# 4T_-.net
KiCad netlist of a schematic drawn in EasyEDA Pro
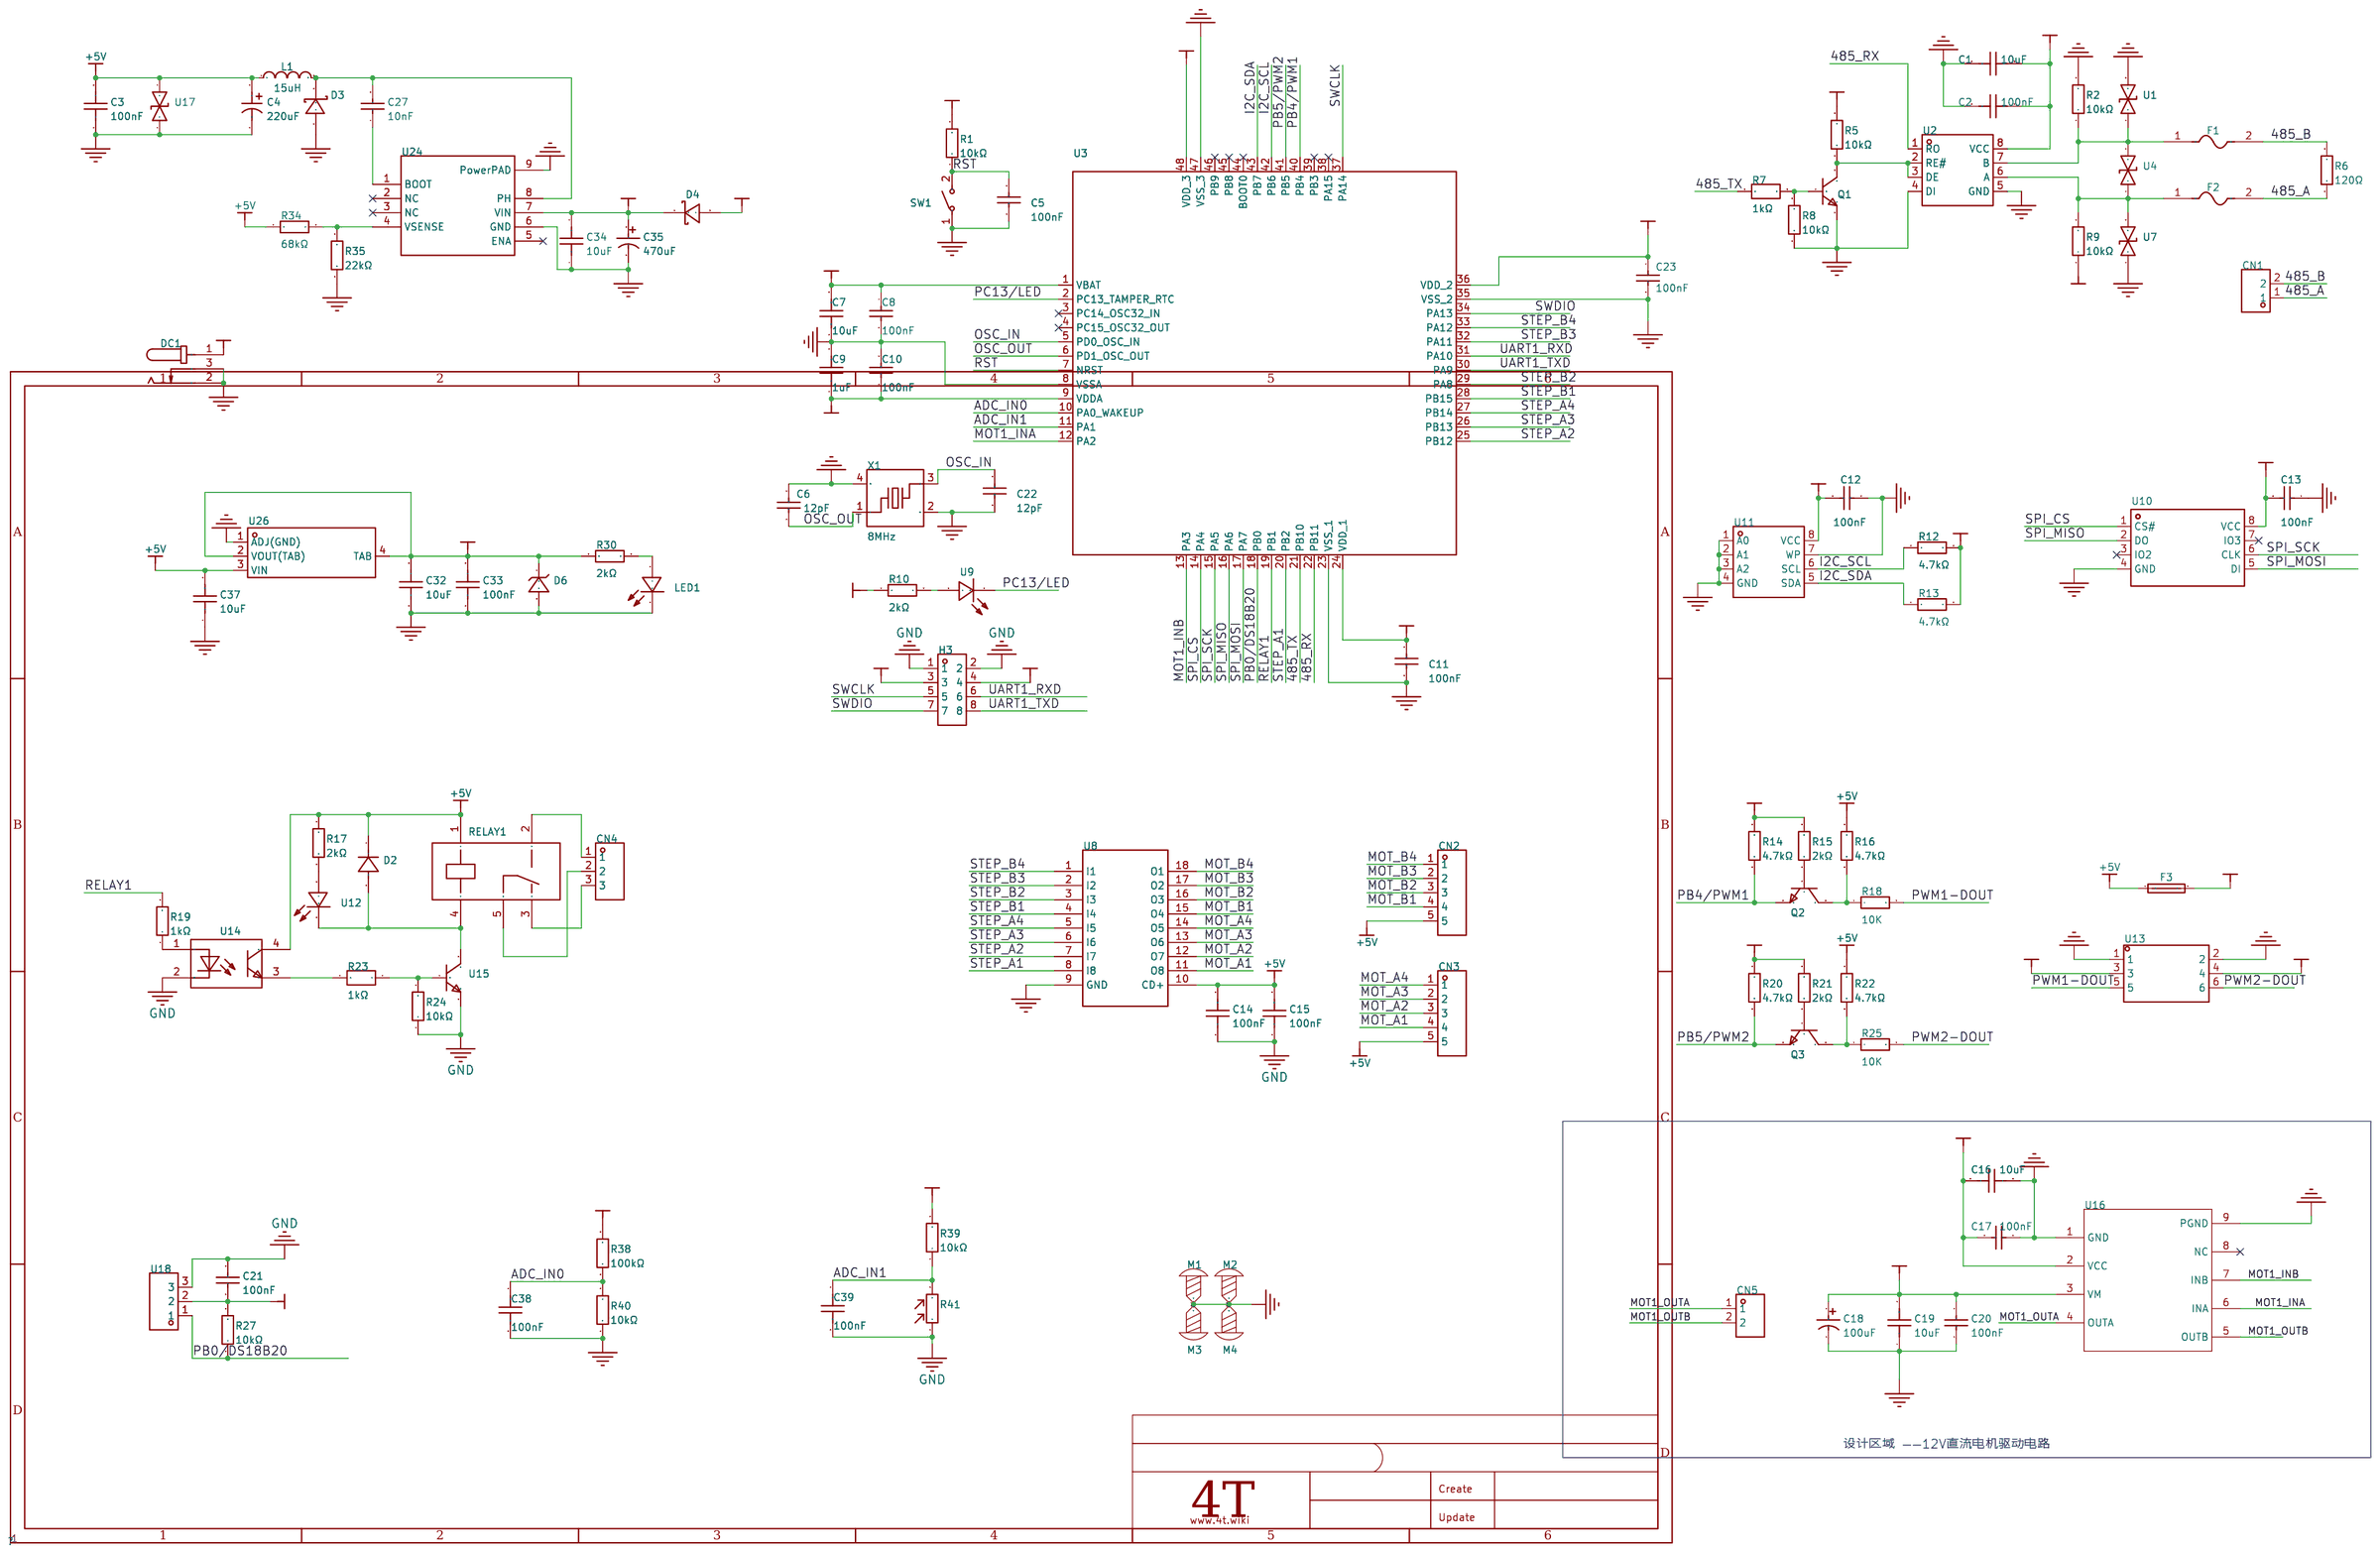
[diagram p0: schematic sheet]

(export (version "E")
  (design (tool "Eeschema 10.0.6"))
  (components
    (comp (ref "C1")
      (value "10uF")
      (footprint "easyedapro:C0603")
      (fields
        (field (name "Manufacturer Part") "CC0603KRX5R6BB106")
        (field (name "Manufacturer") "YAGEO(国巨)")
      )
      (libsource (lib "easyedapro") (part "CC0603KRX5R6BB106"))
    )
    (comp (ref "C2") (value "100nF") (libsource (lib "easyedapro") (part "CC0603KRX7R9BB104")))
    (comp (ref "C3")
      (value "100nF")
      (footprint "easyedapro:C0805")
      (fields
        (field (name "Manufacturer Part") "CC0805KRX7R9BB104")
        (field (name "Manufacturer") "YAGEO(国巨)")
      )
      (libsource (lib "easyedapro") (part "CC0805KRX7R9BB104"))
    )
    (comp (ref "C4")
      (value "220uF")
      (footprint "easyedapro:CAP-SMD_BD6.3-L6.6-W6.6-FD")
      (fields (field (name "Manufacturer Part") "189RV0019") (field (name "Manufacturer") "KNSCHA(科尼盛)"))
      (libsource (lib "easyedapro") (part "189RV0019"))
    )
    (comp (ref "C5") (value "100nF") (libsource (lib "easyedapro") (part "CC0603KRX7R8BB104")))
    (comp (ref "C6")
      (value "12pF")
      (footprint "easyedapro:C0603")
      (fields
        (field (name "Manufacturer Part") "CL10C120JB8NNNC")
        (field (name "Manufacturer") "SAMSUNG(三星)")
      )
      (libsource (lib "easyedapro") (part "CL10C120JB8NNNC"))
    )
    (comp (ref "C7")
      (value "10uF")
      (footprint "easyedapro:C0603")
      (fields
        (field (name "Manufacturer Part") "CL10A106KP8NNNC")
        (field (name "Manufacturer") "SAMSUNG(三星)")
      )
      (libsource (lib "easyedapro") (part "CL10A106KP8NNNC"))
    )
    (comp (ref "C8") (value "100nF") (libsource (lib "easyedapro") (part "CC0603KRX7R8BB104")))
    (comp (ref "C9")
      (value "1uF")
      (footprint "easyedapro:C0603")
      (fields
        (field (name "Manufacturer Part") "CC0603KRX7R9BB105")
        (field (name "Manufacturer") "YAGEO(国巨)")
      )
      (libsource (lib "easyedapro") (part "CC0603KRX7R9BB105"))
    )
    (comp (ref "C10") (value "100nF") (libsource (lib "easyedapro") (part "CC0603KRX7R8BB104")))
    (comp (ref "C11") (value "100nF") (libsource (lib "easyedapro") (part "CC0603KRX7R8BB104")))
    (comp (ref "C12") (value "100nF") (libsource (lib "easyedapro") (part "CC0603KRX7R8BB104")))
    (comp (ref "C13") (value "100nF") (libsource (lib "easyedapro") (part "CC0603KRX7R8BB104")))
    (comp (ref "C14")
      (value "100nF")
      (footprint "easyedapro:C0805")
      (fields
        (field (name "Manufacturer Part") "CL21A226MAQNNNE")
        (field (name "Manufacturer") "SAMSUNG(三星)")
      )
      (libsource (lib "easyedapro") (part "CL21A226MAQNNNE"))
    )
    (comp (ref "C15")
      (value "100nF")
      (footprint "easyedapro:C0805")
      (fields
        (field (name "Manufacturer Part") "CL21A226MAQNNNE")
        (field (name "Manufacturer") "SAMSUNG(三星)")
      )
      (libsource (lib "easyedapro") (part "CL21A226MAQNNNE"))
    )
    (comp (ref "C16")
      (value "10uF")
      (footprint "easyedapro:C0603")
      (fields
        (field (name "Manufacturer Part") "CL10A106MA8NRNC")
        (field (name "Manufacturer") "SAMSUNG(三星)")
      )
      (libsource (lib "easyedapro") (part "CL10A106MA8NRNC"))
    )
    (comp (ref "C17")
      (value "100nF")
      (footprint "easyedapro:C0603")
      (fields
        (field (name "Manufacturer Part") "CC0603KRX7R8BB104")
        (field (name "Manufacturer") "YAGEO(国巨)")
      )
      (libsource (lib "easyedapro") (part "CC0603KRX7R8BB104"))
    )
    (comp (ref "C18")
      (value "100uF")
      (footprint "easyedapro:CAP-SMD_BD6.3-L6.6-W6.6-LS7.2-R-RD")
      (fields (field (name "Manufacturer Part") "RVE1V101M0607") (field (name "Manufacturer") "ROQANG(容强)"))
      (libsource (lib "easyedapro") (part "RVE1V101M0607-C99837"))
    )
    (comp (ref "C19")
      (value "10uF")
      (footprint "easyedapro:C0603")
      (fields
        (field (name "Manufacturer Part") "CL10A106MA8NRNC")
        (field (name "Manufacturer") "SAMSUNG(三星)")
      )
      (libsource (lib "easyedapro") (part "CL10A106MA8NRNC"))
    )
    (comp (ref "C20")
      (value "100nF")
      (footprint "easyedapro:C0603")
      (fields
        (field (name "Manufacturer Part") "CC0603KRX7R8BB104")
        (field (name "Manufacturer") "YAGEO(国巨)")
      )
      (libsource (lib "easyedapro") (part "CC0603KRX7R8BB104"))
    )
    (comp (ref "C21") (value "100nF") (libsource (lib "easyedapro") (part "CC0603KRX7R8BB104")))
    (comp (ref "C22")
      (value "12pF")
      (footprint "easyedapro:C0603")
      (fields
        (field (name "Manufacturer Part") "CL10C120JB8NNNC")
        (field (name "Manufacturer") "SAMSUNG(三星)")
      )
      (libsource (lib "easyedapro") (part "CL10C120JB8NNNC"))
    )
    (comp (ref "C23") (value "100nF") (libsource (lib "easyedapro") (part "CC0603KRX7R8BB104")))
    (comp (ref "C27")
      (value "10nF")
      (footprint "easyedapro:C0603")
      (fields (field (name "Manufacturer Part") "0603B103K500NT") (field (name "Manufacturer") "FH(风华)"))
      (libsource (lib "easyedapro") (part "0603B103K500NT"))
    )
    (comp (ref "C32")
      (value "10uF")
      (footprint "easyedapro:C0603")
      (fields
        (field (name "Manufacturer Part") "CC0603MRX5R8BB106")
        (field (name "Manufacturer") "YAGEO(国巨)")
      )
      (libsource (lib "easyedapro") (part "CC0603MRX5R8BB106"))
    )
    (comp (ref "C33") (value "100nF") (libsource (lib "") (part "CC0603KRX7R9BB104_1")))
    (comp (ref "C34")
      (value "10uF")
      (footprint "easyedapro:C0805")
      (fields
        (field (name "Manufacturer Part") "GRM21BR61H106KE43L")
        (field (name "Manufacturer") "muRata(村田)")
      )
      (libsource (lib "easyedapro") (part "GRM21BR61H106KE43L"))
    )
    (comp (ref "C35")
      (value "470uF")
      (footprint "easyedapro:CAP-SMD_BD10.0-L10.3-W10.3-LS11.0-R-RD")
      (fields (field (name "Manufacturer Part") "RVT1V471M1010") (field (name "Manufacturer") "ROQANG(容强)"))
      (libsource (lib "easyedapro") (part "RVT1V471M1010-C72519"))
    )
    (comp (ref "C37")
      (value "10uF")
      (footprint "easyedapro:C0603")
      (fields
        (field (name "Manufacturer Part") "CC0603MRX5R8BB106")
        (field (name "Manufacturer") "YAGEO(国巨)")
      )
      (libsource (lib "easyedapro") (part "CC0603MRX5R8BB106"))
    )
    (comp (ref "C38")
      (value "100nF")
      (footprint "easyedapro:C0603")
      (fields
        (field (name "Manufacturer Part") "CC0603KRX7R9BB104")
        (field (name "Manufacturer") "YAGEO(国巨)")
      )
      (libsource (lib "easyedapro") (part "CC0603KRX7R9BB104"))
    )
    (comp (ref "C39")
      (value "100nF")
      (footprint "easyedapro:C0603")
      (fields
        (field (name "Manufacturer Part") "CC0603KRX7R9BB104")
        (field (name "Manufacturer") "YAGEO(国巨)")
      )
      (libsource (lib "easyedapro") (part "CC0603KRX7R9BB104"))
    )
    (comp (ref "CN1")
      (value "~")
      (footprint "easyedapro:CONN-TH_P5.00_KF2EDGR-5.0-2P")
      (fields (field (name "Manufacturer Part") "KF2EDGR-5.0-2P") (field (name "Manufacturer") "KEFA(科发)"))
      (libsource (lib "easyedapro") (part "KF2EDGR-5.0-2P"))
    )
    (comp (ref "CN2")
      (value "~")
      (footprint "easyedapro:CONN-TH_5P-P2.54_XH-5AW_C2908614")
      (fields (field (name "Manufacturer Part") "XH-5AW") (field (name "Manufacturer") "HCTL(华灿天禄)"))
      (libsource (lib "easyedapro") (part "XH-5AW_C2908614"))
    )
    (comp (ref "CN3")
      (value "~")
      (footprint "easyedapro:CONN-TH_5P-P2.54_XH-5AW_C2908614")
      (fields (field (name "Manufacturer Part") "XH-5AW") (field (name "Manufacturer") "HCTL(华灿天禄)"))
      (libsource (lib "easyedapro") (part "XH-5AW_C2908614"))
    )
    (comp (ref "CN4")
      (value "~")
      (footprint "easyedapro:CONN-TH_3P-P5.00_KF2EDGR-5.0-3P")
      (fields (field (name "Manufacturer Part") "KF2EDGR-5.0-3P") (field (name "Manufacturer") "KEFA(科发)"))
      (libsource (lib "easyedapro") (part "KF2EDGR-5.0-3P"))
    )
    (comp (ref "CN5")
      (value "~")
      (footprint "easyedapro:CONN-TH_2P-P2.50_ZX-XH2.54-2PWZ")
      (fields
        (field (name "Manufacturer Part") "ZX-XH2.54-2PWZ")
        (field (name "Manufacturer") "Megastar(兆星)")
      )
      (libsource (lib "easyedapro") (part "ZX-XH2.54-2PWZ"))
    )
    (comp (ref "D2") (value "1N4007") (libsource (lib "easyedapro") (part "1N4007_C727081")))
    (comp (ref "D3")
      (value "SS34")
      (footprint "easyedapro:SMA_L4.3-W2.6-LS5.2-RD")
      (fields (field (name "Manufacturer") "MDD(辰达半导体)"))
      (libsource (lib "easyedapro") (part "SS34_C8678"))
    )
    (comp (ref "D4")
      (value "SS34")
      (footprint "easyedapro:SMA_L4.3-W2.6-LS5.2-RD")
      (fields (field (name "Manufacturer") "MDD(辰达半导体)"))
      (libsource (lib "easyedapro") (part "SS34_C8678"))
    )
    (comp (ref "D6")
      (value "~")
      (footprint "easyedapro:SMB_L4.3-W3.6-LS5.3-RD")
      (fields (field (name "Manufacturer Part") "SMBJ3.3A") (field (name "Manufacturer") "RUILON(瑞隆源)"))
      (libsource (lib "easyedapro") (part "SMBJ3.3A_C2990571"))
    )
    (comp (ref "DC1")
      (value "~")
      (footprint "easyedapro:CONN-TH_DC-005-2.5A-2.0")
      (fields
        (field (name "Manufacturer Part") "DC-005-2.5A-2.0")
        (field (name "Manufacturer") "XKB Connectivity(中国星坤)")
      )
      (libsource (lib "easyedapro") (part "DC-005-2.5A-2.0"))
    )
    (comp (ref "F1")
      (value "~")
      (footprint "easyedapro:F0805")
      (fields (field (name "Manufacturer Part") "0805L100/12AR") (field (name "Manufacturer") "LUTE(陆特)"))
      (libsource (lib "easyedapro") (part "0805l100/12ar"))
    )
    (comp (ref "F2")
      (value "~")
      (footprint "easyedapro:F0805")
      (fields (field (name "Manufacturer Part") "0805L100/12AR") (field (name "Manufacturer") "LUTE(陆特)"))
      (libsource (lib "easyedapro") (part "0805l100/12ar"))
    )
    (comp (ref "F3")
      (value "~")
      (footprint "easyedapro:F0603")
      (fields (field (name "Manufacturer Part") "BSMD0603L-100") (field (name "Manufacturer") "BHFUSE(佰宏)"))
      (libsource (lib "easyedapro") (part "BSMD0603L-100"))
    )
    (comp (ref "H3")
      (value "~")
      (footprint "easyedapro:HDR-TH_8P-P2.54-V-M-R2-C4-S2.54")
      (fields (field (name "Manufacturer Part") "PZ254V-12-8P") (field (name "Manufacturer") "XFCN(兴飞)"))
      (libsource (lib "easyedapro") (part "PZ254V-12-8P"))
    )
    (comp (ref "L1")
      (value "15uH")
      (footprint "easyedapro:IND-SMD_L7.1-W6.6_SLO0618H")
      (fields
        (field (name "Manufacturer Part") "SLO0630H150MTT")
        (field (name "Manufacturer") "Sunltech(韩国顺磁)")
      )
      (libsource (lib "easyedapro") (part "SLO0630H150MTT"))
    )
    (comp (ref "LED1")
      (value "~")
      (footprint "easyedapro:LED0603-RD")
      (fields (field (name "Manufacturer Part") "KT-0603R") (field (name "Manufacturer") "KENTO"))
      (libsource (lib "easyedapro") (part "KT-0603R"))
    )
    (comp (ref "M1")
      (value "~")
      (footprint "easyedapro:LQ_M3螺丝")
      (description "Round,210")
      (libsource (lib "easyedapro") (part "M3螺丝孔"))
    )
    (comp (ref "M2")
      (value "~")
      (footprint "easyedapro:LQ_M3螺丝")
      (description "Round,210")
      (libsource (lib "easyedapro") (part "M3螺丝孔"))
    )
    (comp (ref "M3")
      (value "~")
      (footprint "easyedapro:LQ_M3螺丝")
      (description "Round,210")
      (libsource (lib "easyedapro") (part "M3螺丝孔"))
    )
    (comp (ref "M4")
      (value "~")
      (footprint "easyedapro:LQ_M3螺丝")
      (description "Round,210")
      (libsource (lib "easyedapro") (part "M3螺丝孔"))
    )
    (comp (ref "Q1")
      (value "~")
      (footprint "easyedapro:SOT-23-3_L2.9-W1.3-P1.90-LS2.4-BR")
      (fields (field (name "Manufacturer Part") "MMBT3904") (field (name "Manufacturer") "宏迦橙"))
      (libsource (lib "easyedapro") (part "MMBT3904_C7420353"))
    )
    (comp (ref "Q2")
      (value "S8050-J3Y")
      (footprint "easyedapro:SOT-23-3_L2.9-W1.6-P1.90-LS2.8-BR")
      (fields (field (name "Manufacturer Part") "S8050") (field (name "Manufacturer") "CJ(江苏长电/长晶)"))
      (libsource (lib "easyedapro") (part "S8050_C105433"))
    )
    (comp (ref "Q3")
      (value "S8050-J3Y")
      (footprint "easyedapro:SOT-23-3_L2.9-W1.6-P1.90-LS2.8-BR")
      (fields (field (name "Manufacturer Part") "S8050") (field (name "Manufacturer") "CJ(江苏长电/长晶)"))
      (libsource (lib "easyedapro") (part "S8050_C105433"))
    )
    (comp (ref "R1")
      (value "10kΩ")
      (footprint "easyedapro:R0603")
      (fields
        (field (name "Manufacturer Part") "0603WAF1002T5E")
        (field (name "Manufacturer") "UNI-ROYAL(厚声)")
      )
      (libsource (lib "easyedapro") (part "0603WAF1002T5E"))
    )
    (comp (ref "R2") (value "10kΩ") (libsource (lib "easyedapro") (part "RC0603JR-0710KL")))
    (comp (ref "R5")
      (value "10kΩ")
      (footprint "easyedapro:R0603")
      (fields (field (name "Manufacturer Part") "RC0603JR-0710KL") (field (name "Manufacturer") "YAGEO(国巨)"))
      (libsource (lib "easyedapro") (part "RC0603JR-0710KL"))
    )
    (comp (ref "R6")
      (value "120Ω")
      (footprint "easyedapro:R0805")
      (fields
        (field (name "Manufacturer Part") "0805W8F1200T5E")
        (field (name "Manufacturer") "UNI-ROYAL(厚声)")
      )
      (libsource (lib "easyedapro") (part "0805W8F1200T5E"))
    )
    (comp (ref "R7")
      (value "1kΩ")
      (footprint "easyedapro:R0603")
      (fields (field (name "Manufacturer Part") "RT0603BRE071KL") (field (name "Manufacturer") "YAGEO(国巨)"))
      (libsource (lib "easyedapro") (part "RT0603BRE071KL"))
    )
    (comp (ref "R8")
      (value "10kΩ")
      (footprint "easyedapro:R0603")
      (fields (field (name "Manufacturer Part") "RC0603JR-0710KL") (field (name "Manufacturer") "YAGEO(国巨)"))
      (libsource (lib "easyedapro") (part "RC0603JR-0710KL"))
    )
    (comp (ref "R9") (value "10kΩ") (libsource (lib "easyedapro") (part "RC0603JR-0710KL")))
    (comp (ref "R10")
      (value "2kΩ")
      (footprint "easyedapro:R0603")
      (fields
        (field (name "Manufacturer Part") "0603WAF2001T5E")
        (field (name "Manufacturer") "UNI-ROYAL(厚声)")
      )
      (libsource (lib "easyedapro") (part "0603WAF2001T5E"))
    )
    (comp (ref "R12")
      (value "4.7kΩ")
      (footprint "easyedapro:R0603")
      (fields (field (name "Manufacturer Part") "RC0603FR-074K7L") (field (name "Manufacturer") "YAGEO(国巨)"))
      (libsource (lib "easyedapro") (part "RC0603FR-074K7L"))
    )
    (comp (ref "R13")
      (value "4.7kΩ")
      (footprint "easyedapro:R0603")
      (fields (field (name "Manufacturer Part") "RC0603FR-074K7L") (field (name "Manufacturer") "YAGEO(国巨)"))
      (libsource (lib "easyedapro") (part "RC0603FR-074K7L"))
    )
    (comp (ref "R14")
      (value "4.7kΩ")
      (footprint "easyedapro:R0603")
      (fields (field (name "Manufacturer Part") "RC0603FR-074K7L") (field (name "Manufacturer") "YAGEO(国巨)"))
      (libsource (lib "easyedapro") (part "RC0603FR-074K7L"))
    )
    (comp (ref "R15")
      (value "2kΩ")
      (footprint "easyedapro:R0603")
      (fields (field (name "Manufacturer Part") "RC0603FR-072KL") (field (name "Manufacturer") "YAGEO(国巨)"))
      (libsource (lib "easyedapro") (part "RC0603FR-072KL"))
    )
    (comp (ref "R16")
      (value "4.7kΩ")
      (footprint "easyedapro:R0603")
      (fields (field (name "Manufacturer Part") "RC0603FR-074K7L") (field (name "Manufacturer") "YAGEO(国巨)"))
      (libsource (lib "easyedapro") (part "RC0603FR-074K7L"))
    )
    (comp (ref "R17")
      (value "2kΩ")
      (footprint "easyedapro:R0603")
      (fields
        (field (name "Manufacturer Part") "0603WAF2001T5E")
        (field (name "Manufacturer") "UNI-ROYAL(厚声)")
      )
      (libsource (lib "easyedapro") (part "0603WAF2001T5E"))
    )
    (comp (ref "R18")
      (value "10K")
      (footprint "easyedapro:R0603")
      (fields (field (name "Manufacturer Part") "RC0603FR-071KL") (field (name "Manufacturer") "YAGEO(国巨)"))
      (libsource (lib "easyedapro") (part "RC0603FR-071KL"))
    )
    (comp (ref "R19") (value "1kΩ") (libsource (lib "easyedapro") (part "RC0603FR-071KL")))
    (comp (ref "R20")
      (value "4.7kΩ")
      (footprint "easyedapro:R0603")
      (fields (field (name "Manufacturer Part") "RC0603FR-074K7L") (field (name "Manufacturer") "YAGEO(国巨)"))
      (libsource (lib "easyedapro") (part "RC0603FR-074K7L"))
    )
    (comp (ref "R21")
      (value "2kΩ")
      (footprint "easyedapro:R0603")
      (fields (field (name "Manufacturer Part") "RC0603FR-072KL") (field (name "Manufacturer") "YAGEO(国巨)"))
      (libsource (lib "easyedapro") (part "RC0603FR-072KL"))
    )
    (comp (ref "R22")
      (value "4.7kΩ")
      (footprint "easyedapro:R0603")
      (fields (field (name "Manufacturer Part") "RC0603FR-074K7L") (field (name "Manufacturer") "YAGEO(国巨)"))
      (libsource (lib "easyedapro") (part "RC0603FR-074K7L"))
    )
    (comp (ref "R23")
      (value "1kΩ")
      (footprint "easyedapro:R0603")
      (fields (field (name "Manufacturer Part") "RT0603BRE071KL") (field (name "Manufacturer") "YAGEO(国巨)"))
      (libsource (lib "easyedapro") (part "RT0603BRE071KL"))
    )
    (comp (ref "R24")
      (value "10kΩ")
      (footprint "easyedapro:R0603")
      (fields
        (field (name "Manufacturer Part") "0603WAF1002T5E")
        (field (name "Manufacturer") "UNI-ROYAL(厚声)")
      )
      (libsource (lib "easyedapro") (part "0603WAF1002T5E"))
    )
    (comp (ref "R25")
      (value "10K")
      (footprint "easyedapro:R0603")
      (fields (field (name "Manufacturer Part") "RC0603FR-071KL") (field (name "Manufacturer") "YAGEO(国巨)"))
      (libsource (lib "easyedapro") (part "RC0603FR-071KL"))
    )
    (comp (ref "R27")
      (value "10kΩ")
      (footprint "easyedapro:R0603")
      (fields
        (field (name "Manufacturer Part") "0603WAF1002T5E")
        (field (name "Manufacturer") "UNI-ROYAL(厚声)")
      )
      (libsource (lib "easyedapro") (part "0603WAF1002T5E"))
    )
    (comp (ref "R30") (value "2kΩ") (libsource (lib "easyedapro") (part "0603WAF2001T5E")))
    (comp (ref "R34")
      (value "68kΩ")
      (footprint "easyedapro:R0603")
      (fields
        (field (name "Manufacturer Part") "0603WAF6802T5E")
        (field (name "Manufacturer") "UNI-ROYAL(厚声)")
      )
      (libsource (lib "easyedapro") (part "0603WAF6802T5E"))
    )
    (comp (ref "R35")
      (value "22kΩ")
      (footprint "easyedapro:R0603")
      (fields (field (name "Manufacturer Part") "RC0603FR-0722KL") (field (name "Manufacturer") "YAGEO(国巨)"))
      (libsource (lib "easyedapro") (part "RC0603FR-0722KL"))
    )
    (comp (ref "R38")
      (value "100kΩ")
      (footprint "easyedapro:R0603")
      (fields (field (name "Manufacturer Part") "RC0603FR-07100KL") (field (name "Manufacturer") "YAGEO(国巨)"))
      (libsource (lib "easyedapro") (part "RC0603FR-07100KL"))
    )
    (comp (ref "R39")
      (value "10kΩ")
      (footprint "easyedapro:R0603")
      (fields
        (field (name "Manufacturer Part") "0603WAF1002T5E")
        (field (name "Manufacturer") "UNI-ROYAL(厚声)")
      )
      (libsource (lib "easyedapro") (part "0603WAF1002T5E"))
    )
    (comp (ref "R40")
      (value "10kΩ")
      (footprint "easyedapro:R0603")
      (fields
        (field (name "Manufacturer Part") "0603WAF1002T5E")
        (field (name "Manufacturer") "UNI-ROYAL(厚声)")
      )
      (libsource (lib "easyedapro") (part "0603WAF1002T5E"))
    )
    (comp (ref "R41") (value "~") (libsource (lib "easyedapro") (part "GL5516")))
    (comp (ref "RELAY1")
      (value "~")
      (footprint "easyedapro:RELAY-TH_SRD-XXVDC-XL-C")
      (fields (field (name "Manufacturer Part") "SRD-12VDC-SL-C") (field (name "Manufacturer") "松乐"))
      (libsource (lib "easyedapro") (part "SRD-12VDC-SL-C"))
    )
    (comp (ref "SW1")
      (value "~")
      (footprint "easyedapro:SW-SMD_L6.0-W3.5-LS8.0")
      (fields
        (field (name "Manufacturer Part") "GT-TC060B-H025-L1")
        (field (name "Manufacturer") "G-Switch(品赞)")
      )
      (libsource (lib "easyedapro") (part "GT-TC060B-H025-L1"))
    )
    (comp (ref "U1")
      (value "~")
      (footprint "easyedapro:SOD-123FL_L2.8-W1.8-LS3.7-BI")
      (fields (field (name "Manufacturer Part") "SMF6.0CA") (field (name "Manufacturer") "Liown(里阳半导体)"))
      (libsource (lib "easyedapro") (part "SMF6.0CA_C2990473"))
    )
    (comp (ref "U2")
      (value "~")
      (footprint "easyedapro:SOP-8_L4.9-W3.9-P1.27-LS6.0-BL")
      (fields (field (name "Manufacturer Part") "SP3485EN-MS") (field (name "Manufacturer") "MSKSEMI(美森科)"))
      (libsource (lib "easyedapro") (part "SP3485EN-MS"))
    )
    (comp (ref "U3")
      (value "~")
      (footprint "easyedapro:TQFP-48_L7.0-W7.0-P0.50-LS9.0-BL")
      (fields
        (field (name "Manufacturer Part") "GD32F103C8T6")
        (field (name "Manufacturer") "GigaDevice(兆易创新)")
      )
      (libsource (lib "easyedapro") (part "GD32F103C8T6"))
    )
    (comp (ref "U4")
      (value "~")
      (footprint "easyedapro:SOD-123FL_L2.8-W1.8-LS3.7-BI")
      (fields (field (name "Manufacturer Part") "SMF6.0CA") (field (name "Manufacturer") "Liown(里阳半导体)"))
      (libsource (lib "easyedapro") (part "SMF6.0CA_C2990473"))
    )
    (comp (ref "U7")
      (value "~")
      (footprint "easyedapro:SOD-123FL_L2.8-W1.8-LS3.7-BI")
      (fields (field (name "Manufacturer Part") "SMF6.0CA") (field (name "Manufacturer") "Liown(里阳半导体)"))
      (libsource (lib "easyedapro") (part "SMF6.0CA_C2990473"))
    )
    (comp (ref "U8")
      (value "~")
      (footprint "easyedapro:DIP-18_L23.0-W6.5-P2.54-LS7.6-BL")
      (fields (field (name "Manufacturer Part") "ULN2803G-D18-T") (field (name "Manufacturer") "UTC(友顺)"))
      (libsource (lib "easyedapro") (part "ULN2803G-D18-T"))
    )
    (comp (ref "U9")
      (value "~")
      (footprint "easyedapro:LED-TH_BD3.9-P2.54-RD_GREEN")
      (fields (field (name "Manufacturer Part") "L-3N4GD") (field (name "Manufacturer") "PARALIGHT(光鼎)"))
      (libsource (lib "easyedapro") (part "L-3N4GD"))
    )
    (comp (ref "U10")
      (value "~")
      (footprint "easyedapro:SOIC-8_L5.3-W5.3-P1.27-LS8.0-BL")
      (fields (field (name "Manufacturer Part") "W25Q128JVSIQ") (field (name "Manufacturer") "WINBOND(华邦)"))
      (libsource (lib "easyedapro") (part "W25Q128JVSIQTR"))
    )
    (comp (ref "U11")
      (value "AT24C02")
      (footprint "easyedapro:SOP-8_L5.0-W4.0-P1.27-LS6.0-BL")
      (fields (field (name "Manufacturer") "IDCHIP(英锐芯)"))
      (libsource (lib "easyedapro") (part "AT24C02"))
    )
    (comp (ref "U12")
      (value "~")
      (footprint "easyedapro:LED-TH_BD3.9-P2.54-RD_GREEN")
      (fields (field (name "Manufacturer Part") "L-3N4GD") (field (name "Manufacturer") "PARALIGHT(光鼎)"))
      (libsource (lib "easyedapro") (part "L-3N4GD"))
    )
    (comp (ref "U13")
      (value "~")
      (footprint "easyedapro:HDR-TH_6P-P2.54-H-R2-C3-S2.54-W10.0_MTP125-203R1")
      (fields (field (name "Manufacturer Part") "MTP125-1203R1") (field (name "Manufacturer") "MINTRON(明硕)"))
      (libsource (lib "easyedapro") (part "MTP125-203R1"))
    )
    (comp (ref "U14")
      (value "GX817C-S")
      (footprint "easyedapro:SOP-4_L6.5-W4.6-P2.54-LS10.2-TR")
      (fields (field (name "Manufacturer") "国芯佳品"))
      (libsource (lib "easyedapro") (part "GX817C-S"))
    )
    (comp (ref "U15")
      (value "~")
      (footprint "easyedapro:SOT-23-3_L2.9-W1.3-P1.90-LS2.4-BR")
      (fields (field (name "Manufacturer Part") "SS8050") (field (name "Manufacturer") "宏迦橙"))
      (libsource (lib "easyedapro") (part "SS8050_C7420370"))
    )
    (comp (ref "U16") (value "~") (libsource (lib "easyedapro") (part "BDR")))
    (comp (ref "U17")
      (value "~")
      (footprint "easyedapro:SOD-123FL_L2.8-W1.8-LS3.7-BI")
      (fields (field (name "Manufacturer Part") "SMF6.0CA") (field (name "Manufacturer") "Liown(里阳半导体)"))
      (libsource (lib "easyedapro") (part "SMF6.0CA_C2990473"))
    )
    (comp (ref "U18")
      (value "~")
      (footprint "easyedapro:CONN-TH_3P-P2.50_BX-XH2.54-3PWZ")
      (fields (field (name "Manufacturer Part") "BX-XH2.54-3PWZ") (field (name "Manufacturer") "Bossie(博锡)"))
      (libsource (lib "easyedapro") (part "BX-XH2.54-3P WZ"))
    )
    (comp (ref "U24")
      (value "~")
      (footprint "easyedapro:ESOP-8_L4.9-W3.9-P1.27-LS6.0-TL-EP")
      (fields (field (name "Manufacturer Part") "TPS5430DDAR") (field (name "Manufacturer") "TI(德州仪器)"))
      (libsource (lib "easyedapro") (part "TPS5430DDAR"))
    )
    (comp (ref "U26")
      (value "~")
      (footprint "easyedapro:SOT-223-4_L6.5-W3.5-P2.30-LS7.0-BR")
      (fields (field (name "Manufacturer Part") "AMS1117-3.3") (field (name "Manufacturer") "UMW(友台半导体)"))
      (libsource (lib "easyedapro") (part "AMS1117-3.3_C347222"))
    )
    (comp (ref "X1")
      (value "8MHz")
      (footprint "easyedapro:CRYSTAL-SMD_4P-L3.2-W2.5-BL")
      (fields (field (name "Manufacturer Part") "X32258MOB4SI") (field (name "Manufacturer") "YXC(扬兴晶振)"))
      (libsource (lib "easyedapro") (part "X32258MOB4SI"))
    )
  )
  (nets
    (net (code "1") (name "+5V") (class "Default")
      (node (ref "C14") (pin "2") (pinfunction "2_2") (pintype "unspecified"))
      (node (ref "C15") (pin "2") (pinfunction "2_2") (pintype "unspecified"))
      (node (ref "C3") (pin "2") (pinfunction "2_2") (pintype "unspecified"))
      (node (ref "C37") (pin "2") (pinfunction "2_2") (pintype "input"))
      (node (ref "C4") (pin "1") (pinfunction "1_1") (pintype "input"))
      (node (ref "CN2") (pin "5") (pinfunction "5_5") (pintype "unspecified"))
      (node (ref "CN3") (pin "5") (pinfunction "5_5") (pintype "unspecified"))
      (node (ref "D2") (pin "1") (pinfunction "K_1") (pintype "unspecified"))
      (node (ref "F3") (pin "1") (pinfunction "1_1") (pintype "unspecified"))
      (node (ref "L1") (pin "1") (pinfunction "1_1") (pintype "unspecified"))
      (node (ref "R16") (pin "1") (pinfunction "1_1") (pintype "input"))
      (node (ref "R17") (pin "1") (pinfunction "1_1") (pintype "input"))
      (node (ref "R22") (pin "1") (pinfunction "1_1") (pintype "input"))
      (node (ref "R34") (pin "1") (pinfunction "1_1") (pintype "input"))
      (node (ref "RELAY1") (pin "1") (pinfunction "1_1") (pintype "input"))
      (node (ref "U14") (pin "4") (pinfunction "C_4") (pintype "unspecified"))
      (node (ref "U17") (pin "1") (pinfunction "1_1") (pintype "unspecified"))
      (node (ref "U26") (pin "3") (pinfunction "VIN_3") (pintype "unspecified"))
      (node (ref "U8") (pin "10") (pinfunction "CD+_10") (pintype "unspecified"))
    )
    (net (code "2") (name "+5V-OUT") (class "Default")
      (node (ref "F3") (pin "2") (pinfunction "2_2") (pintype "unspecified"))
      (node (ref "U13") (pin "3") (pinfunction "3_3") (pintype "input"))
      (node (ref "U13") (pin "4") (pinfunction "4_4") (pintype "input"))
    )
    (net (code "3") (name "+12V") (class "Default")
      (node (ref "C18") (pin "1") (pinfunction "1_1") (pintype "input"))
      (node (ref "C19") (pin "2") (pinfunction "2_2") (pintype "unspecified"))
      (node (ref "C20") (pin "1") (pinfunction "1_1") (pintype "input"))
      (node (ref "C34") (pin "2") (pinfunction "2_2") (pintype "unspecified"))
      (node (ref "C35") (pin "1") (pinfunction "1_1") (pintype "input"))
      (node (ref "D4") (pin "1") (pinfunction "K_1") (pintype "unspecified"))
      (node (ref "U16") (pin "3") (pinfunction "VM_3") (pintype "input"))
      (node (ref "U24") (pin "7") (pinfunction "VIN_7") (pintype "unspecified"))
    )
    (net (code "4") (name "/485_A") (class "Default")
      (node (ref "CN1") (pin "1") (pinfunction "1_1") (pintype "unspecified"))
      (node (ref "F2") (pin "2") (pinfunction "2_2") (pintype "unspecified"))
      (node (ref "R6") (pin "1") (pinfunction "1_1") (pintype "input"))
    )
    (net (code "5") (name "/485_B") (class "Default")
      (node (ref "CN1") (pin "2") (pinfunction "2_2") (pintype "unspecified"))
      (node (ref "F1") (pin "2") (pinfunction "2_2") (pintype "unspecified"))
      (node (ref "R6") (pin "2") (pinfunction "2_2") (pintype "input"))
    )
    (net (code "6") (name "/485_RX") (class "Default")
      (node (ref "U2") (pin "1") (pinfunction "RO_1") (pintype "unspecified"))
      (node (ref "U3") (pin "22") (pinfunction "PB11_22") (pintype "unspecified"))
    )
    (net (code "7") (name "/485_TX") (class "Default")
      (node (ref "R7") (pin "1") (pinfunction "1_1") (pintype "unspecified"))
      (node (ref "U3") (pin "21") (pinfunction "PB10_21") (pintype "unspecified"))
    )
    (net (code "8") (name "/ADC_IN0") (class "Default")
      (node (ref "C38") (pin "1") (pinfunction "1_1") (pintype "unspecified"))
      (node (ref "R38") (pin "1") (pinfunction "1_1") (pintype "unspecified"))
      (node (ref "R40") (pin "2") (pinfunction "2_2") (pintype "input"))
      (node (ref "U3") (pin "10") (pinfunction "PA0_WAKEUP_10") (pintype "unspecified"))
    )
    (net (code "9") (name "/ADC_IN1") (class "Default")
      (node (ref "C39") (pin "1") (pinfunction "1_1") (pintype "unspecified"))
      (node (ref "R39") (pin "1") (pinfunction "1_1") (pintype "input"))
      (node (ref "R41") (pin "2") (pinfunction "2_2") (pintype "input"))
      (node (ref "U3") (pin "11") (pinfunction "PA1_11") (pintype "unspecified"))
    )
    (net (code "10") (name "/I2C_SCL") (class "Default")
      (node (ref "R12") (pin "1") (pinfunction "1_1") (pintype "input"))
      (node (ref "U11") (pin "6") (pinfunction "SCL_6") (pintype "unspecified"))
      (node (ref "U3") (pin "42") (pinfunction "PB6_42") (pintype "unspecified"))
    )
    (net (code "11") (name "/I2C_SDA") (class "Default")
      (node (ref "R13") (pin "1") (pinfunction "1_1") (pintype "input"))
      (node (ref "U11") (pin "5") (pinfunction "SDA_5") (pintype "unspecified"))
      (node (ref "U3") (pin "43") (pinfunction "PB7_43") (pintype "unspecified"))
    )
    (net (code "12") (name "/MOT1_INA") (class "Default")
      (node (ref "U16") (pin "6") (pinfunction "INA_6") (pintype "input"))
      (node (ref "U3") (pin "12") (pinfunction "PA2_12") (pintype "unspecified"))
    )
    (net (code "13") (name "/MOT1_INB") (class "Default")
      (node (ref "U16") (pin "7") (pinfunction "INB_7") (pintype "input"))
      (node (ref "U3") (pin "13") (pinfunction "PA3_13") (pintype "unspecified"))
    )
    (net (code "14") (name "/MOT1_OUTA") (class "Default")
      (node (ref "CN5") (pin "1") (pinfunction "1_1") (pintype "unspecified"))
      (node (ref "U16") (pin "4") (pinfunction "OUTA_4") (pintype "input"))
    )
    (net (code "15") (name "/MOT1_OUTB") (class "Default")
      (node (ref "CN5") (pin "2") (pinfunction "2_2") (pintype "unspecified"))
      (node (ref "U16") (pin "5") (pinfunction "OUTB_5") (pintype "input"))
    )
    (net (code "16") (name "/MOT_A1") (class "Default")
      (node (ref "CN3") (pin "4") (pinfunction "4_4") (pintype "unspecified"))
      (node (ref "U8") (pin "11") (pinfunction "O8_11") (pintype "unspecified"))
    )
    (net (code "17") (name "/MOT_A2") (class "Default")
      (node (ref "CN3") (pin "3") (pinfunction "3_3") (pintype "unspecified"))
      (node (ref "U8") (pin "12") (pinfunction "O7_12") (pintype "unspecified"))
    )
    (net (code "18") (name "/MOT_A3") (class "Default")
      (node (ref "CN3") (pin "2") (pinfunction "2_2") (pintype "unspecified"))
      (node (ref "U8") (pin "13") (pinfunction "O6_13") (pintype "unspecified"))
    )
    (net (code "19") (name "/MOT_A4") (class "Default")
      (node (ref "CN3") (pin "1") (pinfunction "1_1") (pintype "unspecified"))
      (node (ref "U8") (pin "14") (pinfunction "O5_14") (pintype "unspecified"))
    )
    (net (code "20") (name "/MOT_B1") (class "Default")
      (node (ref "CN2") (pin "4") (pinfunction "4_4") (pintype "unspecified"))
      (node (ref "U8") (pin "15") (pinfunction "O4_15") (pintype "unspecified"))
    )
    (net (code "21") (name "/MOT_B2") (class "Default")
      (node (ref "CN2") (pin "3") (pinfunction "3_3") (pintype "unspecified"))
      (node (ref "U8") (pin "16") (pinfunction "O3_16") (pintype "unspecified"))
    )
    (net (code "22") (name "/MOT_B3") (class "Default")
      (node (ref "CN2") (pin "2") (pinfunction "2_2") (pintype "unspecified"))
      (node (ref "U8") (pin "17") (pinfunction "O2_17") (pintype "unspecified"))
    )
    (net (code "23") (name "/MOT_B4") (class "Default")
      (node (ref "CN2") (pin "1") (pinfunction "1_1") (pintype "unspecified"))
      (node (ref "U8") (pin "18") (pinfunction "O1_18") (pintype "unspecified"))
    )
    (net (code "24") (name "/OSC_IN") (class "Default")
      (node (ref "C22") (pin "2") (pinfunction "2_2") (pintype "input"))
      (node (ref "U3") (pin "5") (pinfunction "PD0_OSC_IN_5") (pintype "unspecified"))
      (node (ref "X1") (pin "3") (pinfunction "3_3") (pintype "input"))
    )
    (net (code "25") (name "/OSC_OUT") (class "Default")
      (node (ref "C6") (pin "1") (pinfunction "1_1") (pintype "input"))
      (node (ref "U3") (pin "6") (pinfunction "PD1_OSC_OUT_6") (pintype "unspecified"))
      (node (ref "X1") (pin "1") (pinfunction "1_1") (pintype "input"))
    )
    (net (code "26") (name "/PB0{slash}DS18B20") (class "Default")
      (node (ref "R27") (pin "1") (pinfunction "1_1") (pintype "input"))
      (node (ref "U18") (pin "1") (pinfunction "1_1") (pintype "unspecified"))
      (node (ref "U3") (pin "18") (pinfunction "PB0_18") (pintype "unspecified"))
    )
    (net (code "27") (name "/PB4{slash}PWM1") (class "Default")
      (node (ref "Q2") (pin "2") (pinfunction "2_2") (pintype "input"))
      (node (ref "R14") (pin "2") (pinfunction "2_2") (pintype "input"))
      (node (ref "U3") (pin "40") (pinfunction "PB4_40") (pintype "unspecified"))
    )
    (net (code "28") (name "/PB5{slash}PWM2") (class "Default")
      (node (ref "Q3") (pin "2") (pinfunction "2_2") (pintype "input"))
      (node (ref "R20") (pin "2") (pinfunction "2_2") (pintype "input"))
      (node (ref "U3") (pin "41") (pinfunction "PB5_41") (pintype "unspecified"))
    )
    (net (code "29") (name "/PC13{slash}LED") (class "Default")
      (node (ref "U3") (pin "2") (pinfunction "PC13_TAMPER_RTC_2") (pintype "unspecified"))
      (node (ref "U9") (pin "1") (pinfunction "C_1") (pintype "unspecified"))
    )
    (net (code "30") (name "/PWM1-DOUT") (class "Default")
      (node (ref "R18") (pin "2") (pinfunction "2_2") (pintype "input"))
      (node (ref "U13") (pin "5") (pinfunction "5_5") (pintype "input"))
    )
    (net (code "31") (name "/PWM2-DOUT") (class "Default")
      (node (ref "R25") (pin "2") (pinfunction "2_2") (pintype "input"))
      (node (ref "U13") (pin "6") (pinfunction "6_6") (pintype "input"))
    )
    (net (code "32") (name "/RELAY1") (class "Default")
      (node (ref "R19") (pin "2") (pinfunction "2_2") (pintype "input"))
      (node (ref "U3") (pin "19") (pinfunction "PB1_19") (pintype "unspecified"))
    )
    (net (code "33") (name "/RST") (class "Default")
      (node (ref "C5") (pin "1") (pinfunction "1_1") (pintype "input"))
      (node (ref "R1") (pin "1") (pinfunction "1_1") (pintype "input"))
      (node (ref "SW1") (pin "2") (pinfunction "2_2") (pintype "unspecified"))
      (node (ref "U3") (pin "7") (pinfunction "NRST_7") (pintype "unspecified"))
    )
    (net (code "34") (name "/SPI_CS") (class "Default")
      (node (ref "U10") (pin "1") (pinfunction "CS#_1") (pintype "unspecified"))
      (node (ref "U3") (pin "14") (pinfunction "PA4_14") (pintype "unspecified"))
    )
    (net (code "35") (name "/SPI_MISO") (class "Default")
      (node (ref "U10") (pin "2") (pinfunction "DO_2") (pintype "unspecified"))
      (node (ref "U3") (pin "16") (pinfunction "PA6_16") (pintype "unspecified"))
    )
    (net (code "36") (name "/SPI_MOSI") (class "Default")
      (node (ref "U10") (pin "5") (pinfunction "DI_5") (pintype "unspecified"))
      (node (ref "U3") (pin "17") (pinfunction "PA7_17") (pintype "unspecified"))
    )
    (net (code "37") (name "/SPI_SCK") (class "Default")
      (node (ref "U10") (pin "6") (pinfunction "CLK_6") (pintype "unspecified"))
      (node (ref "U3") (pin "15") (pinfunction "PA5_15") (pintype "unspecified"))
    )
    (net (code "38") (name "/STEP_A1") (class "Default")
      (node (ref "U3") (pin "20") (pinfunction "PB2_20") (pintype "unspecified"))
      (node (ref "U8") (pin "8") (pinfunction "I8_8") (pintype "input"))
    )
    (net (code "39") (name "/STEP_A2") (class "Default")
      (node (ref "U3") (pin "25") (pinfunction "PB12_25") (pintype "unspecified"))
      (node (ref "U8") (pin "7") (pinfunction "I7_7") (pintype "input"))
    )
    (net (code "40") (name "/STEP_A3") (class "Default")
      (node (ref "U3") (pin "26") (pinfunction "PB13_26") (pintype "unspecified"))
      (node (ref "U8") (pin "6") (pinfunction "I6_6") (pintype "input"))
    )
    (net (code "41") (name "/STEP_A4") (class "Default")
      (node (ref "U3") (pin "27") (pinfunction "PB14_27") (pintype "unspecified"))
      (node (ref "U8") (pin "5") (pinfunction "I5_5") (pintype "input"))
    )
    (net (code "42") (name "/STEP_B1") (class "Default")
      (node (ref "U3") (pin "28") (pinfunction "PB15_28") (pintype "unspecified"))
      (node (ref "U8") (pin "4") (pinfunction "I4_4") (pintype "input"))
    )
    (net (code "43") (name "/STEP_B2") (class "Default")
      (node (ref "U3") (pin "29") (pinfunction "PA8_29") (pintype "unspecified"))
      (node (ref "U8") (pin "3") (pinfunction "I3_3") (pintype "input"))
    )
    (net (code "44") (name "/STEP_B3") (class "Default")
      (node (ref "U3") (pin "32") (pinfunction "PA11_32") (pintype "unspecified"))
      (node (ref "U8") (pin "2") (pinfunction "I2_2") (pintype "input"))
    )
    (net (code "45") (name "/STEP_B4") (class "Default")
      (node (ref "U3") (pin "33") (pinfunction "PA12_33") (pintype "unspecified"))
      (node (ref "U8") (pin "1") (pinfunction "I1_1") (pintype "input"))
    )
    (net (code "46") (name "/SWCLK") (class "Default")
      (node (ref "H3") (pin "5") (pinfunction "5_5") (pintype "unspecified"))
      (node (ref "U3") (pin "37") (pinfunction "PA14_37") (pintype "unspecified"))
    )
    (net (code "47") (name "/SWDIO") (class "Default")
      (node (ref "H3") (pin "7") (pinfunction "7_7") (pintype "unspecified"))
      (node (ref "U3") (pin "34") (pinfunction "PA13_34") (pintype "unspecified"))
    )
    (net (code "48") (name "/UART1_RXD") (class "Default")
      (node (ref "H3") (pin "6") (pinfunction "6_6") (pintype "unspecified"))
      (node (ref "U3") (pin "31") (pinfunction "PA10_31") (pintype "unspecified"))
    )
    (net (code "49") (name "/UART1_TXD") (class "Default")
      (node (ref "H3") (pin "8") (pinfunction "8_8") (pintype "unspecified"))
      (node (ref "U3") (pin "30") (pinfunction "PA9_30") (pintype "unspecified"))
    )
    (net (code "50") (name "3V3") (class "Default")
      (node (ref "C1") (pin "1") (pinfunction "1_1") (pintype "unspecified"))
      (node (ref "C10") (pin "1") (pinfunction "1_1") (pintype "input"))
      (node (ref "C11") (pin "1") (pinfunction "1_1") (pintype "input"))
      (node (ref "C12") (pin "1") (pinfunction "1_1") (pintype "input"))
      (node (ref "C13") (pin "2") (pinfunction "2_2") (pintype "input"))
      (node (ref "C16") (pin "1") (pinfunction "1_1") (pintype "unspecified"))
      (node (ref "C17") (pin "2") (pinfunction "2_2") (pintype "input"))
      (node (ref "C2") (pin "1") (pinfunction "1_1") (pintype "unspecified"))
      (node (ref "C21") (pin "2") (pinfunction "2_2") (pintype "input"))
      (node (ref "C23") (pin "1") (pinfunction "1_1") (pintype "input"))
      (node (ref "C32") (pin "2") (pinfunction "2_2") (pintype "input"))
      (node (ref "C33") (pin "2") (pinfunction "2_2") (pintype "input"))
      (node (ref "C7") (pin "2") (pinfunction "2_2") (pintype "unspecified"))
      (node (ref "C8") (pin "1") (pinfunction "1_1") (pintype "input"))
      (node (ref "C9") (pin "1") (pinfunction "1_1") (pintype "unspecified"))
      (node (ref "D6") (pin "1") (pinfunction "C_1") (pintype "unspecified"))
      (node (ref "H3") (pin "3") (pinfunction "3_3") (pintype "unspecified"))
      (node (ref "H3") (pin "4") (pinfunction "4_4") (pintype "unspecified"))
      (node (ref "R1") (pin "2") (pinfunction "2_2") (pintype "input"))
      (node (ref "R10") (pin "1") (pinfunction "1_1") (pintype "input"))
      (node (ref "R12") (pin "2") (pinfunction "2_2") (pintype "input"))
      (node (ref "R13") (pin "2") (pinfunction "2_2") (pintype "input"))
      (node (ref "R14") (pin "1") (pinfunction "1_1") (pintype "input"))
      (node (ref "R15") (pin "2") (pinfunction "2_2") (pintype "input"))
      (node (ref "R20") (pin "1") (pinfunction "1_1") (pintype "input"))
      (node (ref "R21") (pin "2") (pinfunction "2_2") (pintype "input"))
      (node (ref "R27") (pin "2") (pinfunction "2_2") (pintype "input"))
      (node (ref "R30") (pin "2") (pinfunction "2_2") (pintype "input"))
      (node (ref "R39") (pin "2") (pinfunction "2_2") (pintype "input"))
      (node (ref "R5") (pin "2") (pinfunction "2_2") (pintype "input"))
      (node (ref "R9") (pin "1") (pinfunction "1_1") (pintype "input"))
      (node (ref "U10") (pin "8") (pinfunction "VCC_8") (pintype "unspecified"))
      (node (ref "U11") (pin "8") (pinfunction "VCC_8") (pintype "unspecified"))
      (node (ref "U16") (pin "2") (pinfunction "VCC_2") (pintype "input"))
      (node (ref "U18") (pin "2") (pinfunction "2_2") (pintype "unspecified"))
      (node (ref "U2") (pin "8") (pinfunction "VCC_8") (pintype "unspecified"))
      (node (ref "U26") (pin "2") (pinfunction "VOUT(TAB)_2") (pintype "unspecified"))
      (node (ref "U26") (pin "4") (pinfunction "TAB_4") (pintype "unspecified"))
      (node (ref "U3") (pin "1") (pinfunction "VBAT_1") (pintype "unspecified"))
      (node (ref "U3") (pin "24") (pinfunction "VDD_1_24") (pintype "unspecified"))
      (node (ref "U3") (pin "36") (pinfunction "VDD_2_36") (pintype "unspecified"))
      (node (ref "U3") (pin "48") (pinfunction "VDD_3_48") (pintype "unspecified"))
      (node (ref "U3") (pin "9") (pinfunction "VDDA_9") (pintype "unspecified"))
    )
    (net (code "51") (name "GND") (class "Default")
      (node (ref "C1") (pin "2") (pinfunction "2_2") (pintype "unspecified"))
      (node (ref "C10") (pin "2") (pinfunction "2_2") (pintype "input"))
      (node (ref "C11") (pin "2") (pinfunction "2_2") (pintype "input"))
      (node (ref "C12") (pin "2") (pinfunction "2_2") (pintype "input"))
      (node (ref "C13") (pin "1") (pinfunction "1_1") (pintype "input"))
      (node (ref "C14") (pin "1") (pinfunction "1_1") (pintype "unspecified"))
      (node (ref "C15") (pin "1") (pinfunction "1_1") (pintype "unspecified"))
      (node (ref "C16") (pin "2") (pinfunction "2_2") (pintype "unspecified"))
      (node (ref "C17") (pin "1") (pinfunction "1_1") (pintype "input"))
      (node (ref "C18") (pin "2") (pinfunction "2_2") (pintype "input"))
      (node (ref "C19") (pin "1") (pinfunction "1_1") (pintype "unspecified"))
      (node (ref "C2") (pin "2") (pinfunction "2_2") (pintype "unspecified"))
      (node (ref "C20") (pin "2") (pinfunction "2_2") (pintype "input"))
      (node (ref "C21") (pin "1") (pinfunction "1_1") (pintype "input"))
      (node (ref "C22") (pin "1") (pinfunction "1_1") (pintype "input"))
      (node (ref "C23") (pin "2") (pinfunction "2_2") (pintype "input"))
      (node (ref "C3") (pin "1") (pinfunction "1_1") (pintype "unspecified"))
      (node (ref "C32") (pin "1") (pinfunction "1_1") (pintype "input"))
      (node (ref "C33") (pin "1") (pinfunction "1_1") (pintype "input"))
      (node (ref "C34") (pin "1") (pinfunction "1_1") (pintype "unspecified"))
      (node (ref "C35") (pin "2") (pinfunction "2_2") (pintype "input"))
      (node (ref "C37") (pin "1") (pinfunction "1_1") (pintype "input"))
      (node (ref "C38") (pin "2") (pinfunction "2_2") (pintype "unspecified"))
      (node (ref "C39") (pin "2") (pinfunction "2_2") (pintype "unspecified"))
      (node (ref "C4") (pin "2") (pinfunction "2_2") (pintype "input"))
      (node (ref "C5") (pin "2") (pinfunction "2_2") (pintype "input"))
      (node (ref "C6") (pin "2") (pinfunction "2_2") (pintype "input"))
      (node (ref "C7") (pin "1") (pinfunction "1_1") (pintype "unspecified"))
      (node (ref "C8") (pin "2") (pinfunction "2_2") (pintype "input"))
      (node (ref "C9") (pin "2") (pinfunction "2_2") (pintype "unspecified"))
      (node (ref "D3") (pin "2") (pinfunction "A_2") (pintype "unspecified"))
      (node (ref "D6") (pin "2") (pinfunction "A_2") (pintype "unspecified"))
      (node (ref "DC1") (pin "2") (pinfunction "2_2") (pintype "unspecified"))
      (node (ref "DC1") (pin "3") (pinfunction "3_3") (pintype "unspecified"))
      (node (ref "H3") (pin "1") (pinfunction "1_1") (pintype "unspecified"))
      (node (ref "H3") (pin "2") (pinfunction "2_2") (pintype "unspecified"))
      (node (ref "LED1") (pin "1") (pinfunction "K_1") (pintype "unspecified"))
      (node (ref "M1") (pin "1") (pinfunction "1_1") (pintype "input"))
      (node (ref "M2") (pin "1") (pinfunction "1_1") (pintype "input"))
      (node (ref "M3") (pin "1") (pinfunction "1_1") (pintype "input"))
      (node (ref "M4") (pin "1") (pinfunction "1_1") (pintype "input"))
      (node (ref "Q1") (pin "2") (pinfunction "E_2") (pintype "unspecified"))
      (node (ref "R2") (pin "2") (pinfunction "2_2") (pintype "input"))
      (node (ref "R24") (pin "1") (pinfunction "1_1") (pintype "input"))
      (node (ref "R35") (pin "1") (pinfunction "1_1") (pintype "input"))
      (node (ref "R40") (pin "1") (pinfunction "1_1") (pintype "input"))
      (node (ref "R41") (pin "1") (pinfunction "1_1") (pintype "input"))
      (node (ref "R8") (pin "1") (pinfunction "1_1") (pintype "input"))
      (node (ref "SW1") (pin "1") (pinfunction "1_1") (pintype "unspecified"))
      (node (ref "U1") (pin "2") (pinfunction "2_2") (pintype "unspecified"))
      (node (ref "U10") (pin "4") (pinfunction "GND_4") (pintype "unspecified"))
      (node (ref "U11") (pin "1") (pinfunction "A0_1") (pintype "unspecified"))
      (node (ref "U11") (pin "2") (pinfunction "A1_2") (pintype "unspecified"))
      (node (ref "U11") (pin "3") (pinfunction "A2_3") (pintype "unspecified"))
      (node (ref "U11") (pin "4") (pinfunction "GND_4") (pintype "unspecified"))
      (node (ref "U11") (pin "7") (pinfunction "WP_7") (pintype "unspecified"))
      (node (ref "U13") (pin "1") (pinfunction "1_1") (pintype "input"))
      (node (ref "U13") (pin "2") (pinfunction "2_2") (pintype "input"))
      (node (ref "U14") (pin "2") (pinfunction "C_2") (pintype "unspecified"))
      (node (ref "U15") (pin "2") (pinfunction "E_2") (pintype "input"))
      (node (ref "U16") (pin "1") (pinfunction "GND_1") (pintype "input"))
      (node (ref "U16") (pin "9") (pinfunction "PGND_9") (pintype "input"))
      (node (ref "U17") (pin "2") (pinfunction "2_2") (pintype "unspecified"))
      (node (ref "U18") (pin "3") (pinfunction "3_3") (pintype "unspecified"))
      (node (ref "U2") (pin "4") (pinfunction "DI_4") (pintype "unspecified"))
      (node (ref "U2") (pin "5") (pinfunction "GND_5") (pintype "unspecified"))
      (node (ref "U24") (pin "6") (pinfunction "GND_6") (pintype "unspecified"))
      (node (ref "U24") (pin "9") (pinfunction "PowerPAD_9") (pintype "unspecified"))
      (node (ref "U26") (pin "1") (pinfunction "ADJ(GND)_1") (pintype "unspecified"))
      (node (ref "U3") (pin "23") (pinfunction "VSS_1_23") (pintype "unspecified"))
      (node (ref "U3") (pin "35") (pinfunction "VSS_2_35") (pintype "unspecified"))
      (node (ref "U3") (pin "47") (pinfunction "VSS_3_47") (pintype "unspecified"))
      (node (ref "U3") (pin "8") (pinfunction "VSSA_8") (pintype "unspecified"))
      (node (ref "U7") (pin "1") (pinfunction "1_1") (pintype "unspecified"))
      (node (ref "U8") (pin "9") (pinfunction "GND_9") (pintype "unspecified"))
      (node (ref "X1") (pin "2") (pinfunction "GND_2") (pintype "input"))
      (node (ref "X1") (pin "4") (pinfunction "GND_4") (pintype "input"))
    )
    (net (code "52") (name "Net-(CN4-Pad1)") (class "Default")
      (node (ref "CN4") (pin "1") (pinfunction "1_1") (pintype "unspecified"))
      (node (ref "RELAY1") (pin "2") (pinfunction "2_2") (pintype "input"))
    )
    (net (code "53") (name "Net-(CN4-Pad2)") (class "Default")
      (node (ref "CN4") (pin "2") (pinfunction "2_2") (pintype "unspecified"))
      (node (ref "RELAY1") (pin "5") (pinfunction "5_5") (pintype "input"))
    )
    (net (code "54") (name "Net-(CN4-Pad3)") (class "Default")
      (node (ref "CN4") (pin "3") (pinfunction "3_3") (pintype "unspecified"))
      (node (ref "RELAY1") (pin "3") (pinfunction "3_3") (pintype "input"))
    )
    (net (code "55") (name "Net-(D2-A)") (class "Default")
      (node (ref "D2") (pin "2") (pinfunction "A_2") (pintype "unspecified"))
      (node (ref "RELAY1") (pin "4") (pinfunction "4_4") (pintype "input"))
      (node (ref "U12") (pin "1") (pinfunction "C_1") (pintype "unspecified"))
      (node (ref "U15") (pin "3") (pinfunction "C_3") (pintype "input"))
    )
    (net (code "56") (name "Net-(D3-K)") (class "Default")
      (node (ref "C27") (pin "2") (pinfunction "2_2") (pintype "input"))
      (node (ref "D3") (pin "1") (pinfunction "K_1") (pintype "unspecified"))
      (node (ref "L1") (pin "2") (pinfunction "2_2") (pintype "unspecified"))
      (node (ref "U24") (pin "8") (pinfunction "PH_8") (pintype "unspecified"))
    )
    (net (code "57") (name "Net-(LED1-A)") (class "Default")
      (node (ref "LED1") (pin "2") (pinfunction "A_2") (pintype "unspecified"))
      (node (ref "R30") (pin "1") (pinfunction "1_1") (pintype "input"))
    )
    (net (code "58") (name "Net-(Q1-B)") (class "Default")
      (node (ref "Q1") (pin "1") (pinfunction "B_1") (pintype "unspecified"))
      (node (ref "R7") (pin "2") (pinfunction "2_2") (pintype "unspecified"))
      (node (ref "R8") (pin "2") (pinfunction "2_2") (pintype "input"))
    )
    (net (code "59") (name "Net-(Q1-C)") (class "Default")
      (node (ref "Q1") (pin "3") (pinfunction "C_3") (pintype "unspecified"))
      (node (ref "R5") (pin "1") (pinfunction "1_1") (pintype "input"))
      (node (ref "U2") (pin "2") (pinfunction "RE#_2") (pintype "unspecified"))
      (node (ref "U2") (pin "3") (pinfunction "DE_3") (pintype "unspecified"))
    )
    (net (code "60") (name "Net-(Q2-Pad1)") (class "Default")
      (node (ref "Q2") (pin "1") (pinfunction "1_1") (pintype "input"))
      (node (ref "R15") (pin "1") (pinfunction "1_1") (pintype "input"))
    )
    (net (code "61") (name "Net-(Q2-Pad3)") (class "Default")
      (node (ref "Q2") (pin "3") (pinfunction "3_3") (pintype "input"))
      (node (ref "R16") (pin "2") (pinfunction "2_2") (pintype "input"))
      (node (ref "R18") (pin "1") (pinfunction "1_1") (pintype "input"))
    )
    (net (code "62") (name "Net-(Q3-Pad1)") (class "Default")
      (node (ref "Q3") (pin "1") (pinfunction "1_1") (pintype "input"))
      (node (ref "R21") (pin "1") (pinfunction "1_1") (pintype "input"))
    )
    (net (code "63") (name "Net-(Q3-Pad3)") (class "Default")
      (node (ref "Q3") (pin "3") (pinfunction "3_3") (pintype "input"))
      (node (ref "R22") (pin "2") (pinfunction "2_2") (pintype "input"))
      (node (ref "R25") (pin "1") (pinfunction "1_1") (pintype "input"))
    )
    (net (code "64") (name "Net-(U2-A)") (class "Default")
      (node (ref "F2") (pin "1") (pinfunction "1_1") (pintype "unspecified"))
      (node (ref "R9") (pin "2") (pinfunction "2_2") (pintype "input"))
      (node (ref "U2") (pin "6") (pinfunction "A_6") (pintype "unspecified"))
      (node (ref "U4") (pin "1") (pinfunction "1_1") (pintype "unspecified"))
      (node (ref "U7") (pin "2") (pinfunction "2_2") (pintype "unspecified"))
    )
    (net (code "65") (name "Net-(U2-B)") (class "Default")
      (node (ref "F1") (pin "1") (pinfunction "1_1") (pintype "unspecified"))
      (node (ref "R2") (pin "1") (pinfunction "1_1") (pintype "input"))
      (node (ref "U1") (pin "1") (pinfunction "1_1") (pintype "unspecified"))
      (node (ref "U2") (pin "7") (pinfunction "B_7") (pintype "unspecified"))
      (node (ref "U4") (pin "2") (pinfunction "2_2") (pintype "unspecified"))
    )
    (net (code "66") (name "Net-(U9-A)") (class "Default")
      (node (ref "R10") (pin "2") (pinfunction "2_2") (pintype "input"))
      (node (ref "U9") (pin "2") (pinfunction "A_2") (pintype "unspecified"))
    )
    (net (code "67") (name "Net-(U12-A)") (class "Default")
      (node (ref "R17") (pin "2") (pinfunction "2_2") (pintype "input"))
      (node (ref "U12") (pin "2") (pinfunction "A_2") (pintype "unspecified"))
    )
    (net (code "68") (name "Net-(U14-A)") (class "Default")
      (node (ref "R19") (pin "1") (pinfunction "1_1") (pintype "input"))
      (node (ref "U14") (pin "1") (pinfunction "A_1") (pintype "unspecified"))
    )
    (net (code "69") (name "Net-(U14-E)") (class "Default")
      (node (ref "R23") (pin "2") (pinfunction "2_2") (pintype "unspecified"))
      (node (ref "U14") (pin "3") (pinfunction "E_3") (pintype "unspecified"))
    )
    (net (code "70") (name "Net-(U15-B)") (class "Default")
      (node (ref "R23") (pin "1") (pinfunction "1_1") (pintype "unspecified"))
      (node (ref "R24") (pin "2") (pinfunction "2_2") (pintype "input"))
      (node (ref "U15") (pin "1") (pinfunction "B_1") (pintype "input"))
    )
    (net (code "71") (name "Net-(U24-BOOT)") (class "Default")
      (node (ref "C27") (pin "1") (pinfunction "1_1") (pintype "input"))
      (node (ref "U24") (pin "1") (pinfunction "BOOT_1") (pintype "unspecified"))
    )
    (net (code "72") (name "Net-(U24-VSENSE)") (class "Default")
      (node (ref "R34") (pin "2") (pinfunction "2_2") (pintype "input"))
      (node (ref "R35") (pin "2") (pinfunction "2_2") (pintype "input"))
      (node (ref "U24") (pin "4") (pinfunction "VSENSE_4") (pintype "unspecified"))
    )
    (net (code "73") (name "VIN") (class "Default")
      (node (ref "D4") (pin "2") (pinfunction "A_2") (pintype "unspecified"))
      (node (ref "DC1") (pin "1") (pinfunction "1_1") (pintype "unspecified"))
      (node (ref "R38") (pin "2") (pinfunction "2_2") (pintype "unspecified"))
    )
    (net (code "74") (name "unconnected-(U3-BOOT0-Pad44)") (class "Default")
      (node (ref "U3") (pin "44") (pinfunction "BOOT0_44") (pintype "unspecified+no_connect"))
    )
    (net (code "75") (name "unconnected-(U3-PA15-Pad38)") (class "Default")
      (node (ref "U3") (pin "38") (pinfunction "PA15_38") (pintype "unspecified+no_connect"))
    )
    (net (code "76") (name "unconnected-(U3-PB3-Pad39)") (class "Default")
      (node (ref "U3") (pin "39") (pinfunction "PB3_39") (pintype "unspecified+no_connect"))
    )
    (net (code "77") (name "unconnected-(U3-PB8-Pad45)") (class "Default")
      (node (ref "U3") (pin "45") (pinfunction "PB8_45") (pintype "unspecified+no_connect"))
    )
    (net (code "78") (name "unconnected-(U3-PB9-Pad46)") (class "Default")
      (node (ref "U3") (pin "46") (pinfunction "PB9_46") (pintype "unspecified+no_connect"))
    )
    (net (code "79") (name "unconnected-(U3-PC14_OSC32_IN-Pad3)") (class "Default")
      (node (ref "U3") (pin "3") (pinfunction "PC14_OSC32_IN_3") (pintype "unspecified+no_connect"))
    )
    (net (code "80") (name "unconnected-(U3-PC15_OSC32_OUT-Pad4)") (class "Default")
      (node (ref "U3") (pin "4") (pinfunction "PC15_OSC32_OUT_4") (pintype "unspecified+no_connect"))
    )
    (net (code "81") (name "unconnected-(U10-IO2-Pad3)") (class "Default")
      (node (ref "U10") (pin "3") (pinfunction "IO2_3") (pintype "unspecified+no_connect"))
    )
    (net (code "82") (name "unconnected-(U10-IO3-Pad7)") (class "Default")
      (node (ref "U10") (pin "7") (pinfunction "IO3_7") (pintype "unspecified+no_connect"))
    )
    (net (code "83") (name "unconnected-(U16-NC-Pad8)") (class "Default")
      (node (ref "U16") (pin "8") (pinfunction "NC_8") (pintype "input+no_connect"))
    )
    (net (code "84") (name "unconnected-(U24-ENA-Pad5)") (class "Default")
      (node (ref "U24") (pin "5") (pinfunction "ENA_5") (pintype "unspecified+no_connect"))
    )
    (net (code "85") (name "unconnected-(U24-NC-Pad2)") (class "Default")
      (node (ref "U24") (pin "2") (pinfunction "NC_2") (pintype "unspecified+no_connect"))
    )
    (net (code "86") (name "unconnected-(U24-NC-Pad3)") (class "Default")
      (node (ref "U24") (pin "3") (pinfunction "NC_3") (pintype "unspecified+no_connect"))
    )
  )
)
